# WiFiShield.net
KiCad netlist of a schematic drawn in EAGLE
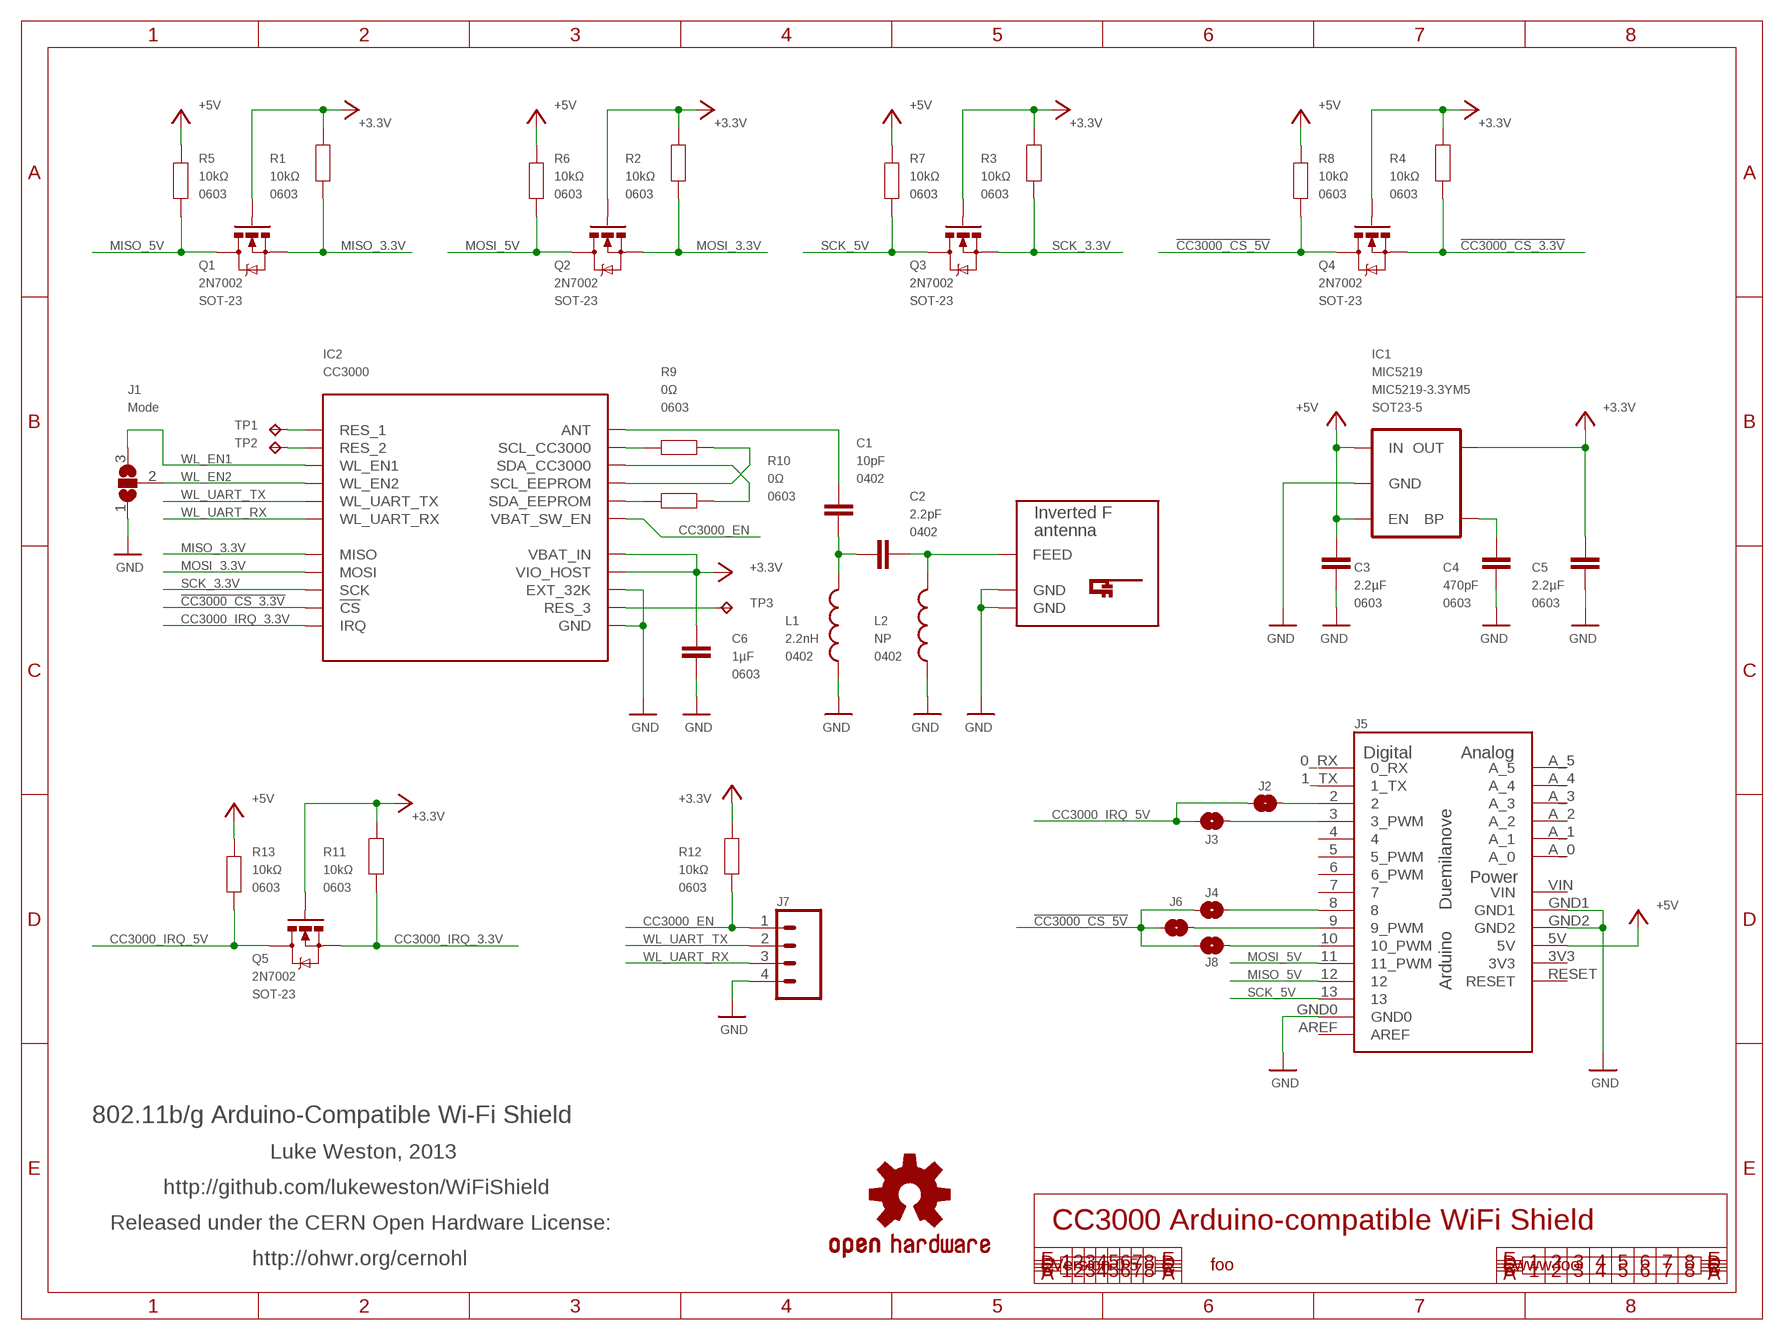
[diagram p0: schematic, sheet 1]

(export (version "E")
  (design (tool "Eeschema 10.0.6"))
  (components
    (comp (ref "A1")
      (value "INVERTED_F_ANTENNA+2")
      (footprint "eagle-import:DN007+2")
      (libsource (lib "eagle-import") (part "INVERTED_F_ANTENNA+2"))
    )
    (comp (ref "C1")
      (value "10pF")
      (footprint "eagle-import:C0402")
      (fields (field (name "PACKAGE") "0402"))
      (libsource (lib "eagle-import") (part "CAP0402"))
    )
    (comp (ref "C2")
      (value "2.2pF")
      (footprint "eagle-import:C0402")
      (fields (field (name "PACKAGE") "0402"))
      (libsource (lib "eagle-import") (part "CAP0402"))
    )
    (comp (ref "C3")
      (value "2.2µF")
      (footprint "eagle-import:0603")
      (fields (field (name "PACKAGE") "0603"))
      (libsource (lib "eagle-import") (part "CAP0603"))
    )
    (comp (ref "C4")
      (value "470pF")
      (footprint "eagle-import:0603")
      (fields (field (name "PACKAGE") "0603"))
      (libsource (lib "eagle-import") (part "CAP0603"))
    )
    (comp (ref "C5")
      (value "2.2µF")
      (footprint "eagle-import:0603")
      (fields (field (name "PACKAGE") "0603"))
      (libsource (lib "eagle-import") (part "CAP0603"))
    )
    (comp (ref "C6")
      (value "1µF")
      (footprint "eagle-import:0603")
      (fields (field (name "PACKAGE") "0603"))
      (libsource (lib "eagle-import") (part "CAP0603"))
    )
    (comp (ref "IC1")
      (value "MIC5219")
      (footprint "eagle-import:SOT23-5")
      (fields (field (name "ID") "MIC5219-3.3YM5") (field (name "PACKAGE") "SOT23-5"))
      (libsource (lib "eagle-import") (part "V_REG_LDOSMD"))
    )
    (comp (ref "IC2")
      (value "CC3000")
      (footprint "eagle-import:CC3000")
      (libsource (lib "eagle-import") (part "CC3000"))
    )
    (comp (ref "J1")
      (value "Mode")
      (footprint "eagle-import:SJ_2")
      (libsource (lib "eagle-import") (part "SJ2W"))
    )
    (comp (ref "J2") (value "SJ") (footprint "eagle-import:SJ") (libsource (lib "eagle-import") (part "SJ")))
    (comp (ref "J3") (value "SJ") (footprint "eagle-import:SJ") (libsource (lib "eagle-import") (part "SJ")))
    (comp (ref "J4") (value "SJ") (footprint "eagle-import:SJ") (libsource (lib "eagle-import") (part "SJ")))
    (comp (ref "J5")
      (value "Arduino-compatible headers")
      (footprint "eagle-import:NO-OUTLINE-OCTAGONAL-NOTEXT")
      (libsource (lib "eagle-import") (part "ARDUINO-USBNO-OUTLINE-NO-TEXT-OCTAGONAL"))
    )
    (comp (ref "J6") (value "SJ") (footprint "eagle-import:SJ") (libsource (lib "eagle-import") (part "SJ")))
    (comp (ref "J7")
      (value "M041.27MM")
      (footprint "eagle-import:1X04-1.27MM")
      (libsource (lib "eagle-import") (part "M041.27MM"))
    )
    (comp (ref "J8") (value "SJ") (footprint "eagle-import:SJ") (libsource (lib "eagle-import") (part "SJ")))
    (comp (ref "L1")
      (value "2.2nH")
      (footprint "eagle-import:C0402")
      (fields (field (name "PACKAGE") "0402"))
      (libsource (lib "eagle-import") (part "INDUCTOR0402"))
    )
    (comp (ref "L2")
      (value "NP")
      (footprint "eagle-import:C0402")
      (fields (field (name "PACKAGE") "0402"))
      (libsource (lib "eagle-import") (part "INDUCTOR0402"))
    )
    (comp (ref "Q1")
      (value "2N7002")
      (footprint "eagle-import:SOT23-3")
      (fields (field (name "PACKAGE") "SOT-23"))
      (libsource (lib "eagle-import") (part "MOSFET-NCHANNELSMD"))
    )
    (comp (ref "Q2")
      (value "2N7002")
      (footprint "eagle-import:SOT23-3")
      (fields (field (name "PACKAGE") "SOT-23"))
      (libsource (lib "eagle-import") (part "MOSFET-NCHANNELSMD"))
    )
    (comp (ref "Q3")
      (value "2N7002")
      (footprint "eagle-import:SOT23-3")
      (fields (field (name "PACKAGE") "SOT-23"))
      (libsource (lib "eagle-import") (part "MOSFET-NCHANNELSMD"))
    )
    (comp (ref "Q4")
      (value "2N7002")
      (footprint "eagle-import:SOT23-3")
      (fields (field (name "PACKAGE") "SOT-23"))
      (libsource (lib "eagle-import") (part "MOSFET-NCHANNELSMD"))
    )
    (comp (ref "Q5")
      (value "2N7002")
      (footprint "eagle-import:SOT23-3")
      (fields (field (name "PACKAGE") "SOT-23"))
      (libsource (lib "eagle-import") (part "MOSFET-NCHANNELSMD"))
    )
    (comp (ref "R1")
      (value "10kΩ")
      (footprint "eagle-import:0603")
      (fields (field (name "PACKAGE") "0603"))
      (libsource (lib "eagle-import") (part "RESISTOR0603"))
    )
    (comp (ref "R2")
      (value "10kΩ")
      (footprint "eagle-import:0603")
      (fields (field (name "PACKAGE") "0603"))
      (libsource (lib "eagle-import") (part "RESISTOR0603"))
    )
    (comp (ref "R3")
      (value "10kΩ")
      (footprint "eagle-import:0603")
      (fields (field (name "PACKAGE") "0603"))
      (libsource (lib "eagle-import") (part "RESISTOR0603"))
    )
    (comp (ref "R4")
      (value "10kΩ")
      (footprint "eagle-import:0603")
      (fields (field (name "PACKAGE") "0603"))
      (libsource (lib "eagle-import") (part "RESISTOR0603"))
    )
    (comp (ref "R5")
      (value "10kΩ")
      (footprint "eagle-import:0603")
      (fields (field (name "PACKAGE") "0603"))
      (libsource (lib "eagle-import") (part "RESISTOR0603"))
    )
    (comp (ref "R6")
      (value "10kΩ")
      (footprint "eagle-import:0603")
      (fields (field (name "PACKAGE") "0603"))
      (libsource (lib "eagle-import") (part "RESISTOR0603"))
    )
    (comp (ref "R7")
      (value "10kΩ")
      (footprint "eagle-import:0603")
      (fields (field (name "PACKAGE") "0603"))
      (libsource (lib "eagle-import") (part "RESISTOR0603"))
    )
    (comp (ref "R8")
      (value "10kΩ")
      (footprint "eagle-import:0603")
      (fields (field (name "PACKAGE") "0603"))
      (libsource (lib "eagle-import") (part "RESISTOR0603"))
    )
    (comp (ref "R9")
      (value "0Ω")
      (footprint "eagle-import:0603")
      (fields (field (name "PACKAGE") "0603"))
      (libsource (lib "eagle-import") (part "RESISTOR0603"))
    )
    (comp (ref "R10")
      (value "0Ω")
      (footprint "eagle-import:0603")
      (fields (field (name "PACKAGE") "0603"))
      (libsource (lib "eagle-import") (part "RESISTOR0603"))
    )
    (comp (ref "R11")
      (value "10kΩ")
      (footprint "eagle-import:0603")
      (fields (field (name "PACKAGE") "0603"))
      (libsource (lib "eagle-import") (part "RESISTOR0603"))
    )
    (comp (ref "R12")
      (value "10kΩ")
      (footprint "eagle-import:0603")
      (fields (field (name "PACKAGE") "0603"))
      (libsource (lib "eagle-import") (part "RESISTOR0603"))
    )
    (comp (ref "R13")
      (value "10kΩ")
      (footprint "eagle-import:0603")
      (fields (field (name "PACKAGE") "0603"))
      (libsource (lib "eagle-import") (part "RESISTOR0603"))
    )
    (comp (ref "SY")
      (value "OSHW-LOGOS")
      (footprint "eagle-import:OSHW-LOGO-S")
      (libsource (lib "eagle-import") (part "OSHW-LOGOS"))
    )
    (comp (ref "TP1")
      (value "TPTP06R")
      (footprint "eagle-import:TP06R")
      (libsource (lib "eagle-import") (part "TPTP06R"))
    )
    (comp (ref "TP2")
      (value "TPTP06R")
      (footprint "eagle-import:TP06R")
      (libsource (lib "eagle-import") (part "TPTP06R"))
    )
    (comp (ref "TP3")
      (value "TPTP06R")
      (footprint "eagle-import:TP06R")
      (libsource (lib "eagle-import") (part "TPTP06R"))
    )
  )
  (nets
    (net (code "1") (name "+3.3V") (class "Default")
      (node (ref "C5") (pin "1") (pinfunction "1_1") (pintype "passive"))
      (node (ref "C6") (pin "2") (pinfunction "2_2") (pintype "passive"))
      (node (ref "IC1") (pin "5") (pinfunction "OUT_5") (pintype "passive"))
      (node (ref "IC2") (pin "19") (pinfunction "VBAT_IN_19") (pintype "bidirectional"))
      (node (ref "IC2") (pin "23") (pinfunction "VIO_HOST_23") (pintype "bidirectional"))
      (node (ref "Q1") (pin "1") (pinfunction "G_1") (pintype "passive"))
      (node (ref "Q2") (pin "1") (pinfunction "G_1") (pintype "passive"))
      (node (ref "Q3") (pin "1") (pinfunction "G_1") (pintype "passive"))
      (node (ref "Q4") (pin "1") (pinfunction "G_1") (pintype "passive"))
      (node (ref "Q5") (pin "1") (pinfunction "G_1") (pintype "passive"))
      (node (ref "R1") (pin "2") (pinfunction "2_2") (pintype "passive"))
      (node (ref "R11") (pin "2") (pinfunction "2_2") (pintype "passive"))
      (node (ref "R12") (pin "2") (pinfunction "2_2") (pintype "passive"))
      (node (ref "R2") (pin "2") (pinfunction "2_2") (pintype "passive"))
      (node (ref "R3") (pin "2") (pinfunction "2_2") (pintype "passive"))
      (node (ref "R4") (pin "2") (pinfunction "2_2") (pintype "passive"))
    )
    (net (code "2") (name "+5V") (class "Default")
      (node (ref "C3") (pin "2") (pinfunction "2_2") (pintype "passive"))
      (node (ref "IC1") (pin "1") (pinfunction "IN_1") (pintype "input"))
      (node (ref "IC1") (pin "3") (pinfunction "EN_3") (pintype "input"))
      (node (ref "J5") (pin "5V") (pinfunction "5V_5V") (pintype "power_in"))
      (node (ref "R13") (pin "2") (pinfunction "2_2") (pintype "passive"))
      (node (ref "R5") (pin "2") (pinfunction "2_2") (pintype "passive"))
      (node (ref "R6") (pin "2") (pinfunction "2_2") (pintype "passive"))
      (node (ref "R7") (pin "2") (pinfunction "2_2") (pintype "passive"))
      (node (ref "R8") (pin "2") (pinfunction "2_2") (pintype "passive"))
    )
    (net (code "3") (name "/3V3") (class "Default")
      (node (ref "J5") (pin "3V3") (pinfunction "3V3_3V3") (pintype "power_in"))
    )
    (net (code "4") (name "/CC3000_EN") (class "Default")
      (node (ref "IC2") (pin "26") (pinfunction "VBAT_SW_EN_26") (pintype "bidirectional"))
      (node (ref "J7") (pin "1") (pinfunction "1_1") (pintype "passive"))
      (node (ref "R12") (pin "1") (pinfunction "1_1") (pintype "passive"))
    )
    (net (code "5") (name "/CC3000_IRQ_3.3V") (class "Default")
      (node (ref "IC2") (pin "14") (pinfunction "IRQ_14") (pintype "bidirectional"))
      (node (ref "Q5") (pin "2") (pinfunction "S_2") (pintype "passive"))
      (node (ref "R11") (pin "1") (pinfunction "1_1") (pintype "passive"))
    )
    (net (code "6") (name "/CC3000_IRQ_5V") (class "Default")
      (node (ref "J2") (pin "1") (pinfunction "1_1") (pintype "passive"))
      (node (ref "J3") (pin "1") (pinfunction "1_1") (pintype "passive"))
      (node (ref "Q5") (pin "3") (pinfunction "D_3") (pintype "passive"))
      (node (ref "R13") (pin "1") (pinfunction "1_1") (pintype "passive"))
    )
    (net (code "7") (name "/MISO_3.3V") (class "Default")
      (node (ref "IC2") (pin "13") (pinfunction "MISO_13") (pintype "bidirectional"))
      (node (ref "Q1") (pin "2") (pinfunction "S_2") (pintype "passive"))
      (node (ref "R1") (pin "1") (pinfunction "1_1") (pintype "passive"))
    )
    (net (code "8") (name "/MISO_5V") (class "Default")
      (node (ref "J5") (pin "12") (pinfunction "12_12") (pintype "bidirectional"))
      (node (ref "Q1") (pin "3") (pinfunction "D_3") (pintype "passive"))
      (node (ref "R5") (pin "1") (pinfunction "1_1") (pintype "passive"))
    )
    (net (code "9") (name "/MOSI_3.3V") (class "Default")
      (node (ref "IC2") (pin "15") (pinfunction "MOSI_15") (pintype "bidirectional"))
      (node (ref "Q2") (pin "2") (pinfunction "S_2") (pintype "passive"))
      (node (ref "R2") (pin "1") (pinfunction "1_1") (pintype "passive"))
    )
    (net (code "10") (name "/MOSI_5V") (class "Default")
      (node (ref "J5") (pin "11") (pinfunction "11_PWM_11") (pintype "bidirectional"))
      (node (ref "Q2") (pin "3") (pinfunction "D_3") (pintype "passive"))
      (node (ref "R6") (pin "1") (pinfunction "1_1") (pintype "passive"))
    )
    (net (code "11") (name "/SCK_3.3V") (class "Default")
      (node (ref "IC2") (pin "17") (pinfunction "SCK_17") (pintype "bidirectional"))
      (node (ref "Q3") (pin "2") (pinfunction "S_2") (pintype "passive"))
      (node (ref "R3") (pin "1") (pinfunction "1_1") (pintype "passive"))
    )
    (net (code "12") (name "/SCK_5V") (class "Default")
      (node (ref "J5") (pin "13") (pinfunction "13_13") (pintype "bidirectional"))
      (node (ref "Q3") (pin "3") (pinfunction "D_3") (pintype "passive"))
      (node (ref "R7") (pin "1") (pinfunction "1_1") (pintype "passive"))
    )
    (net (code "13") (name "/VIN") (class "Default")
      (node (ref "J5") (pin "VIN") (pinfunction "VIN_VIN") (pintype "power_in"))
    )
    (net (code "14") (name "/WL_EN1") (class "Default")
      (node (ref "IC2") (pin "7") (pinfunction "WL_EN1_7") (pintype "bidirectional"))
      (node (ref "J1") (pin "3") (pinfunction "3_3") (pintype "passive"))
    )
    (net (code "15") (name "/WL_EN2") (class "Default")
      (node (ref "IC2") (pin "5") (pinfunction "WL_EN2_5") (pintype "bidirectional"))
      (node (ref "J1") (pin "2") (pinfunction "2_2") (pintype "passive"))
    )
    (net (code "16") (name "/WL_UART_RX") (class "Default")
      (node (ref "IC2") (pin "8") (pinfunction "WL_UART_RX_8") (pintype "bidirectional"))
      (node (ref "J7") (pin "3") (pinfunction "3_3") (pintype "passive"))
    )
    (net (code "17") (name "/WL_UART_TX") (class "Default")
      (node (ref "IC2") (pin "6") (pinfunction "WL_UART_TX_6") (pintype "bidirectional"))
      (node (ref "J7") (pin "2") (pinfunction "2_2") (pintype "passive"))
    )
    (net (code "18") (name "/~{CC3000_CS_3.3V}") (class "Default")
      (node (ref "IC2") (pin "12") (pinfunction "~{CS}_12") (pintype "bidirectional"))
      (node (ref "Q4") (pin "2") (pinfunction "S_2") (pintype "passive"))
      (node (ref "R4") (pin "1") (pinfunction "1_1") (pintype "passive"))
    )
    (net (code "19") (name "/~{CC3000_CS_5V}") (class "Default")
      (node (ref "J4") (pin "1") (pinfunction "1_1") (pintype "passive"))
      (node (ref "J6") (pin "1") (pinfunction "1_1") (pintype "passive"))
      (node (ref "J8") (pin "1") (pinfunction "1_1") (pintype "passive"))
      (node (ref "Q4") (pin "3") (pinfunction "D_3") (pintype "passive"))
      (node (ref "R8") (pin "1") (pinfunction "1_1") (pintype "passive"))
    )
    (net (code "20") (name "GND") (class "Default")
      (node (ref "A1") (pin "GND") (pinfunction "GND_GND") (pintype "bidirectional"))
      (node (ref "A1") (pin "GND@1") (pinfunction "GND_GND@1") (pintype "bidirectional"))
      (node (ref "C3") (pin "1") (pinfunction "1_1") (pintype "passive"))
      (node (ref "C4") (pin "1") (pinfunction "1_1") (pintype "passive"))
      (node (ref "C5") (pin "2") (pinfunction "2_2") (pintype "passive"))
      (node (ref "C6") (pin "1") (pinfunction "1_1") (pintype "passive"))
      (node (ref "IC1") (pin "2") (pinfunction "GND_2") (pintype "input"))
      (node (ref "IC2") (pin "1") (pinfunction "GND_1") (pintype "bidirectional"))
      (node (ref "IC2") (pin "10") (pinfunction "GND_10") (pintype "bidirectional"))
      (node (ref "IC2") (pin "11") (pinfunction "GND_11") (pintype "bidirectional"))
      (node (ref "IC2") (pin "16") (pinfunction "GND_16") (pintype "bidirectional"))
      (node (ref "IC2") (pin "18") (pinfunction "GND_18") (pintype "bidirectional"))
      (node (ref "IC2") (pin "20") (pinfunction "GND_20") (pintype "bidirectional"))
      (node (ref "IC2") (pin "21") (pinfunction "EXT_32K_21") (pintype "bidirectional"))
      (node (ref "IC2") (pin "22") (pinfunction "GND_22") (pintype "bidirectional"))
      (node (ref "IC2") (pin "25") (pinfunction "GND_25") (pintype "bidirectional"))
      (node (ref "IC2") (pin "31") (pinfunction "GND_31") (pintype "bidirectional"))
      (node (ref "IC2") (pin "32") (pinfunction "GND_32") (pintype "bidirectional"))
      (node (ref "IC2") (pin "33") (pinfunction "GND_33") (pintype "bidirectional"))
      (node (ref "IC2") (pin "34") (pinfunction "GND_34") (pintype "bidirectional"))
      (node (ref "IC2") (pin "36") (pinfunction "GND_36") (pintype "bidirectional"))
      (node (ref "IC2") (pin "37") (pinfunction "GND_37") (pintype "bidirectional"))
      (node (ref "IC2") (pin "38") (pinfunction "GND_38") (pintype "bidirectional"))
      (node (ref "IC2") (pin "39") (pinfunction "GND_39") (pintype "bidirectional"))
      (node (ref "IC2") (pin "40") (pinfunction "GND_40") (pintype "bidirectional"))
      (node (ref "IC2") (pin "41") (pinfunction "GND_41") (pintype "bidirectional"))
      (node (ref "IC2") (pin "42") (pinfunction "GND_42") (pintype "bidirectional"))
      (node (ref "IC2") (pin "43") (pinfunction "GND_43") (pintype "bidirectional"))
      (node (ref "IC2") (pin "44") (pinfunction "GND_44") (pintype "bidirectional"))
      (node (ref "IC2") (pin "45") (pinfunction "GND_45") (pintype "bidirectional"))
      (node (ref "IC2") (pin "46") (pinfunction "GND_46") (pintype "bidirectional"))
      (node (ref "IC2") (pin "9") (pinfunction "GND_9") (pintype "bidirectional"))
      (node (ref "J1") (pin "1") (pinfunction "1_1") (pintype "passive"))
      (node (ref "J5") (pin "GND0") (pinfunction "GND0_GND0") (pintype "power_in"))
      (node (ref "J5") (pin "GND1") (pinfunction "GND1_GND1") (pintype "power_in"))
      (node (ref "J5") (pin "GND2") (pinfunction "GND2_GND2") (pintype "power_in"))
      (node (ref "J7") (pin "4") (pinfunction "4_4") (pintype "passive"))
      (node (ref "L1") (pin "2") (pinfunction "2_2") (pintype "passive"))
      (node (ref "L2") (pin "2") (pinfunction "2_2") (pintype "passive"))
    )
    (net (code "21") (name "Net-(A1-PadFEED)") (class "Default")
      (node (ref "A1") (pin "FEED") (pinfunction "FEED_FEED") (pintype "bidirectional"))
      (node (ref "C2") (pin "1") (pinfunction "1_1") (pintype "passive"))
      (node (ref "L2") (pin "1") (pinfunction "1_1") (pintype "passive"))
    )
    (net (code "22") (name "Net-(C1-Pad1)") (class "Default")
      (node (ref "C1") (pin "1") (pinfunction "1_1") (pintype "passive"))
      (node (ref "C2") (pin "2") (pinfunction "2_2") (pintype "passive"))
      (node (ref "L1") (pin "1") (pinfunction "1_1") (pintype "passive"))
    )
    (net (code "23") (name "Net-(IC1-BP)") (class "Default")
      (node (ref "C4") (pin "2") (pinfunction "2_2") (pintype "passive"))
      (node (ref "IC1") (pin "4") (pinfunction "BP_4") (pintype "input"))
    )
    (net (code "24") (name "Net-(IC2-ANT)") (class "Default")
      (node (ref "C1") (pin "2") (pinfunction "2_2") (pintype "passive"))
      (node (ref "IC2") (pin "35") (pinfunction "ANT_35") (pintype "bidirectional"))
    )
    (net (code "25") (name "Net-(IC2-RES_1)") (class "Default")
      (node (ref "IC2") (pin "2") (pinfunction "RES_1_2") (pintype "bidirectional"))
      (node (ref "TP1") (pin "TP") (pinfunction "TP_TP") (pintype "input"))
    )
    (net (code "26") (name "Net-(IC2-RES_2)") (class "Default")
      (node (ref "IC2") (pin "4") (pinfunction "RES_2_4") (pintype "bidirectional"))
      (node (ref "TP2") (pin "TP") (pinfunction "TP_TP") (pintype "input"))
    )
    (net (code "27") (name "Net-(IC2-RES_3)") (class "Default")
      (node (ref "IC2") (pin "24") (pinfunction "RES_3_24") (pintype "bidirectional"))
      (node (ref "TP3") (pin "TP") (pinfunction "TP_TP") (pintype "input"))
    )
    (net (code "28") (name "Net-(IC2-SCL_CC3000)") (class "Default")
      (node (ref "IC2") (pin "30") (pinfunction "SCL_CC3000_30") (pintype "bidirectional"))
      (node (ref "R9") (pin "2") (pinfunction "2_2") (pintype "passive"))
    )
    (net (code "29") (name "Net-(IC2-SCL_EEPROM)") (class "Default")
      (node (ref "IC2") (pin "29") (pinfunction "SCL_EEPROM_29") (pintype "bidirectional"))
      (node (ref "R9") (pin "1") (pinfunction "1_1") (pintype "passive"))
    )
    (net (code "30") (name "Net-(IC2-SDA_CC3000)") (class "Default")
      (node (ref "IC2") (pin "28") (pinfunction "SDA_CC3000_28") (pintype "bidirectional"))
      (node (ref "R10") (pin "1") (pinfunction "1_1") (pintype "passive"))
    )
    (net (code "31") (name "Net-(IC2-SDA_EEPROM)") (class "Default")
      (node (ref "IC2") (pin "27") (pinfunction "SDA_EEPROM_27") (pintype "bidirectional"))
      (node (ref "R10") (pin "2") (pinfunction "2_2") (pintype "passive"))
    )
    (net (code "32") (name "Net-(J2-Pad2)") (class "Default")
      (node (ref "J2") (pin "2") (pinfunction "2_2") (pintype "passive"))
      (node (ref "J5") (pin "2") (pinfunction "2_2") (pintype "bidirectional"))
    )
    (net (code "33") (name "Net-(J4-Pad2)") (class "Default")
      (node (ref "J4") (pin "2") (pinfunction "2_2") (pintype "passive"))
      (node (ref "J5") (pin "8") (pinfunction "8_8") (pintype "bidirectional"))
    )
    (net (code "34") (name "Net-(J5-3_PWM)") (class "Default")
      (node (ref "J3") (pin "2") (pinfunction "2_2") (pintype "passive"))
      (node (ref "J5") (pin "3") (pinfunction "3_PWM_3") (pintype "bidirectional"))
    )
    (net (code "35") (name "Net-(J5-9_PWM)") (class "Default")
      (node (ref "J5") (pin "9") (pinfunction "9_PWM_9") (pintype "bidirectional"))
      (node (ref "J6") (pin "2") (pinfunction "2_2") (pintype "passive"))
    )
    (net (code "36") (name "Net-(J5-10_PWM)") (class "Default")
      (node (ref "J5") (pin "10") (pinfunction "10_PWM_10") (pintype "bidirectional"))
      (node (ref "J8") (pin "2") (pinfunction "2_2") (pintype "passive"))
    )
    (net (code "37") (name "unconnected-(J5-5_PWM-Pad5)") (class "Default")
      (node (ref "J5") (pin "5") (pinfunction "5_PWM_5") (pintype "bidirectional"))
    )
    (net (code "38") (name "unconnected-(J5-6_PWM-Pad6)") (class "Default")
      (node (ref "J5") (pin "6") (pinfunction "6_PWM_6") (pintype "bidirectional"))
    )
    (net (code "39") (name "unconnected-(J5-Pad0_RX)") (class "Default")
      (node (ref "J5") (pin "0_RX") (pinfunction "0_RX_0_RX") (pintype "bidirectional"))
    )
    (net (code "40") (name "unconnected-(J5-Pad1_TX)") (class "Default")
      (node (ref "J5") (pin "1_TX") (pinfunction "1_TX_1_TX") (pintype "bidirectional"))
    )
    (net (code "41") (name "unconnected-(J5-Pad4)") (class "Default")
      (node (ref "J5") (pin "4") (pinfunction "4_4") (pintype "bidirectional"))
    )
    (net (code "42") (name "unconnected-(J5-Pad7)") (class "Default")
      (node (ref "J5") (pin "7") (pinfunction "7_7") (pintype "bidirectional"))
    )
    (net (code "43") (name "unconnected-(J5-PadAREF)") (class "Default")
      (node (ref "J5") (pin "AREF") (pinfunction "AREF_AREF") (pintype "bidirectional"))
    )
    (net (code "44") (name "unconnected-(J5-PadA_0)") (class "Default")
      (node (ref "J5") (pin "A_0") (pinfunction "A_0_A_0") (pintype "input"))
    )
    (net (code "45") (name "unconnected-(J5-PadA_1)") (class "Default")
      (node (ref "J5") (pin "A_1") (pinfunction "A_1_A_1") (pintype "input"))
    )
    (net (code "46") (name "unconnected-(J5-PadA_2)") (class "Default")
      (node (ref "J5") (pin "A_2") (pinfunction "A_2_A_2") (pintype "input"))
    )
    (net (code "47") (name "unconnected-(J5-PadA_3)") (class "Default")
      (node (ref "J5") (pin "A_3") (pinfunction "A_3_A_3") (pintype "input"))
    )
    (net (code "48") (name "unconnected-(J5-PadA_4)") (class "Default")
      (node (ref "J5") (pin "A_4") (pinfunction "A_4_A_4") (pintype "input"))
    )
    (net (code "49") (name "unconnected-(J5-PadA_5)") (class "Default")
      (node (ref "J5") (pin "A_5") (pinfunction "A_5_A_5") (pintype "input"))
    )
    (net (code "50") (name "unconnected-(J5-PadRESET)") (class "Default")
      (node (ref "J5") (pin "RESET") (pinfunction "RESET_RESET") (pintype "input"))
    )
  )
)
